# MRCS-CSNK.net
KiCad netlist of a schematic drawn in EAGLE
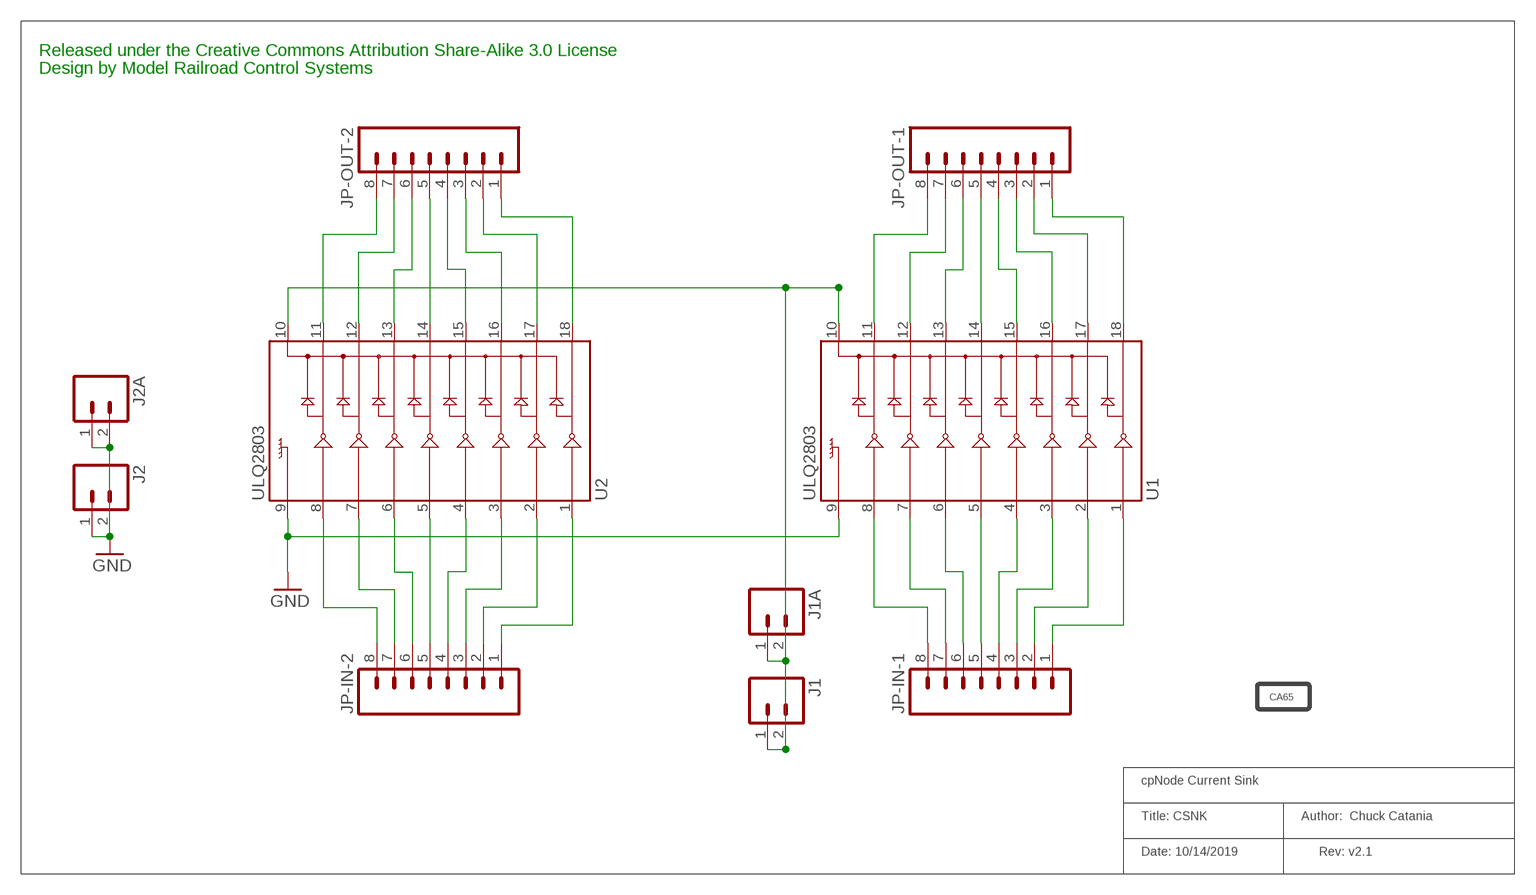
[diagram p0: schematic, sheet 1]

(export (version "E")
  (design (tool "Eeschema 10.0.6"))
  (components
    (comp (ref "J1")
      (value "CONNECTOR-M021X02-LOCK")
      (footprint "eagle-import:1X02_LOCK")
      (libsource (lib "eagle-import") (part "CONNECTOR-M021X02-LOCK"))
    )
    (comp (ref "J1A")
      (value "CONNECTOR-M023.5MM-LOCK")
      (footprint "eagle-import:SCREWTERMINAL-3.5MM-2_LOCK")
      (libsource (lib "eagle-import") (part "CONNECTOR-M023.5MM-LOCK"))
    )
    (comp (ref "J2")
      (value "CONNECTOR-M021X02-LOCK")
      (footprint "eagle-import:1X02_LOCK")
      (libsource (lib "eagle-import") (part "CONNECTOR-M021X02-LOCK"))
    )
    (comp (ref "J2A")
      (value "CONNECTOR-M023.5MM-LOCK")
      (footprint "eagle-import:SCREWTERMINAL-3.5MM-2_LOCK")
      (libsource (lib "eagle-import") (part "CONNECTOR-M023.5MM-LOCK"))
    )
    (comp (ref "JP-IN-1")
      (value "CONNECTOR-M08LOCK")
      (footprint "eagle-import:1X08_LOCK")
      (libsource (lib "eagle-import") (part "CONNECTOR-M08LOCK"))
    )
    (comp (ref "JP-IN-2")
      (value "CONNECTOR-M08LOCK")
      (footprint "eagle-import:1X08_LOCK")
      (libsource (lib "eagle-import") (part "CONNECTOR-M08LOCK"))
    )
    (comp (ref "JP-OUT-1")
      (value "CONNECTOR-M08LOCK")
      (footprint "eagle-import:1X08_LOCK")
      (libsource (lib "eagle-import") (part "CONNECTOR-M08LOCK"))
    )
    (comp (ref "JP-OUT-2")
      (value "CONNECTOR-M08LOCK")
      (footprint "eagle-import:1X08_LOCK")
      (libsource (lib "eagle-import") (part "CONNECTOR-M08LOCK"))
    )
    (comp (ref "PROP65")
      (value "DOC-CA65B")
      (footprint "eagle-import:CA-PROP65-BACK")
      (libsource (lib "eagle-import") (part "DOC-CA65B"))
    )
    (comp (ref "U1")
      (value "ULQ2803")
      (footprint "eagle-import:DIL18")
      (libsource (lib "eagle-import") (part "ULN2803DIP"))
    )
    (comp (ref "U2")
      (value "ULQ2803")
      (footprint "eagle-import:DIL18")
      (libsource (lib "eagle-import") (part "ULN2803DIP"))
    )
  )
  (nets
    (net (code "1") (name "GND") (class "Default")
      (node (ref "J2") (pin "1") (pinfunction "A_1") (pintype "passive"))
      (node (ref "J2") (pin "2") (pinfunction "B_2") (pintype "passive"))
      (node (ref "J2A") (pin "1") (pinfunction "A_1") (pintype "passive"))
      (node (ref "J2A") (pin "2") (pinfunction "B_2") (pintype "passive"))
      (node (ref "U1") (pin "9") (pinfunction "9_9") (pintype "bidirectional"))
      (node (ref "U2") (pin "9") (pinfunction "9_9") (pintype "bidirectional"))
    )
    (net (code "2") (name "Net-(J1-A)") (class "Default")
      (node (ref "J1") (pin "1") (pinfunction "A_1") (pintype "passive"))
      (node (ref "J1") (pin "2") (pinfunction "B_2") (pintype "passive"))
      (node (ref "J1A") (pin "1") (pinfunction "A_1") (pintype "passive"))
      (node (ref "J1A") (pin "2") (pinfunction "B_2") (pintype "passive"))
      (node (ref "U1") (pin "10") (pinfunction "10_10") (pintype "bidirectional"))
      (node (ref "U2") (pin "10") (pinfunction "10_10") (pintype "bidirectional"))
    )
    (net (code "3") (name "Net-(JP-IN-1-Pad1)") (class "Default")
      (node (ref "JP-IN-1") (pin "1") (pinfunction "1_1") (pintype "passive"))
      (node (ref "U1") (pin "1") (pinfunction "1_1") (pintype "bidirectional"))
    )
    (net (code "4") (name "Net-(JP-IN-1-Pad2)") (class "Default")
      (node (ref "JP-IN-1") (pin "2") (pinfunction "2_2") (pintype "passive"))
      (node (ref "U1") (pin "2") (pinfunction "2_2") (pintype "bidirectional"))
    )
    (net (code "5") (name "Net-(JP-IN-1-Pad3)") (class "Default")
      (node (ref "JP-IN-1") (pin "3") (pinfunction "3_3") (pintype "passive"))
      (node (ref "U1") (pin "3") (pinfunction "3_3") (pintype "bidirectional"))
    )
    (net (code "6") (name "Net-(JP-IN-1-Pad4)") (class "Default")
      (node (ref "JP-IN-1") (pin "4") (pinfunction "4_4") (pintype "passive"))
      (node (ref "U1") (pin "4") (pinfunction "4_4") (pintype "bidirectional"))
    )
    (net (code "7") (name "Net-(JP-IN-1-Pad5)") (class "Default")
      (node (ref "JP-IN-1") (pin "5") (pinfunction "5_5") (pintype "passive"))
      (node (ref "U1") (pin "5") (pinfunction "5_5") (pintype "bidirectional"))
    )
    (net (code "8") (name "Net-(JP-IN-1-Pad6)") (class "Default")
      (node (ref "JP-IN-1") (pin "6") (pinfunction "6_6") (pintype "passive"))
      (node (ref "U1") (pin "6") (pinfunction "6_6") (pintype "bidirectional"))
    )
    (net (code "9") (name "Net-(JP-IN-1-Pad7)") (class "Default")
      (node (ref "JP-IN-1") (pin "7") (pinfunction "7_7") (pintype "passive"))
      (node (ref "U1") (pin "7") (pinfunction "7_7") (pintype "bidirectional"))
    )
    (net (code "10") (name "Net-(JP-IN-1-Pad8)") (class "Default")
      (node (ref "JP-IN-1") (pin "8") (pinfunction "8_8") (pintype "passive"))
      (node (ref "U1") (pin "8") (pinfunction "8_8") (pintype "bidirectional"))
    )
    (net (code "11") (name "Net-(JP-IN-2-Pad1)") (class "Default")
      (node (ref "JP-IN-2") (pin "1") (pinfunction "1_1") (pintype "passive"))
      (node (ref "U2") (pin "1") (pinfunction "1_1") (pintype "bidirectional"))
    )
    (net (code "12") (name "Net-(JP-IN-2-Pad2)") (class "Default")
      (node (ref "JP-IN-2") (pin "2") (pinfunction "2_2") (pintype "passive"))
      (node (ref "U2") (pin "2") (pinfunction "2_2") (pintype "bidirectional"))
    )
    (net (code "13") (name "Net-(JP-IN-2-Pad3)") (class "Default")
      (node (ref "JP-IN-2") (pin "3") (pinfunction "3_3") (pintype "passive"))
      (node (ref "U2") (pin "3") (pinfunction "3_3") (pintype "bidirectional"))
    )
    (net (code "14") (name "Net-(JP-IN-2-Pad4)") (class "Default")
      (node (ref "JP-IN-2") (pin "4") (pinfunction "4_4") (pintype "passive"))
      (node (ref "U2") (pin "4") (pinfunction "4_4") (pintype "bidirectional"))
    )
    (net (code "15") (name "Net-(JP-IN-2-Pad5)") (class "Default")
      (node (ref "JP-IN-2") (pin "5") (pinfunction "5_5") (pintype "passive"))
      (node (ref "U2") (pin "5") (pinfunction "5_5") (pintype "bidirectional"))
    )
    (net (code "16") (name "Net-(JP-IN-2-Pad6)") (class "Default")
      (node (ref "JP-IN-2") (pin "6") (pinfunction "6_6") (pintype "passive"))
      (node (ref "U2") (pin "6") (pinfunction "6_6") (pintype "bidirectional"))
    )
    (net (code "17") (name "Net-(JP-IN-2-Pad7)") (class "Default")
      (node (ref "JP-IN-2") (pin "7") (pinfunction "7_7") (pintype "passive"))
      (node (ref "U2") (pin "7") (pinfunction "7_7") (pintype "bidirectional"))
    )
    (net (code "18") (name "Net-(JP-IN-2-Pad8)") (class "Default")
      (node (ref "JP-IN-2") (pin "8") (pinfunction "8_8") (pintype "passive"))
      (node (ref "U2") (pin "8") (pinfunction "8_8") (pintype "bidirectional"))
    )
    (net (code "19") (name "Net-(JP-OUT-1-Pad1)") (class "Default")
      (node (ref "JP-OUT-1") (pin "1") (pinfunction "1_1") (pintype "passive"))
      (node (ref "U1") (pin "18") (pinfunction "18_18") (pintype "bidirectional"))
    )
    (net (code "20") (name "Net-(JP-OUT-1-Pad2)") (class "Default")
      (node (ref "JP-OUT-1") (pin "2") (pinfunction "2_2") (pintype "passive"))
      (node (ref "U1") (pin "17") (pinfunction "17_17") (pintype "bidirectional"))
    )
    (net (code "21") (name "Net-(JP-OUT-1-Pad3)") (class "Default")
      (node (ref "JP-OUT-1") (pin "3") (pinfunction "3_3") (pintype "passive"))
      (node (ref "U1") (pin "16") (pinfunction "16_16") (pintype "bidirectional"))
    )
    (net (code "22") (name "Net-(JP-OUT-1-Pad4)") (class "Default")
      (node (ref "JP-OUT-1") (pin "4") (pinfunction "4_4") (pintype "passive"))
      (node (ref "U1") (pin "15") (pinfunction "15_15") (pintype "bidirectional"))
    )
    (net (code "23") (name "Net-(JP-OUT-1-Pad5)") (class "Default")
      (node (ref "JP-OUT-1") (pin "5") (pinfunction "5_5") (pintype "passive"))
      (node (ref "U1") (pin "14") (pinfunction "14_14") (pintype "bidirectional"))
    )
    (net (code "24") (name "Net-(JP-OUT-1-Pad6)") (class "Default")
      (node (ref "JP-OUT-1") (pin "6") (pinfunction "6_6") (pintype "passive"))
      (node (ref "U1") (pin "13") (pinfunction "13_13") (pintype "bidirectional"))
    )
    (net (code "25") (name "Net-(JP-OUT-1-Pad7)") (class "Default")
      (node (ref "JP-OUT-1") (pin "7") (pinfunction "7_7") (pintype "passive"))
      (node (ref "U1") (pin "12") (pinfunction "12_12") (pintype "bidirectional"))
    )
    (net (code "26") (name "Net-(JP-OUT-1-Pad8)") (class "Default")
      (node (ref "JP-OUT-1") (pin "8") (pinfunction "8_8") (pintype "passive"))
      (node (ref "U1") (pin "11") (pinfunction "11_11") (pintype "bidirectional"))
    )
    (net (code "27") (name "Net-(JP-OUT-2-Pad1)") (class "Default")
      (node (ref "JP-OUT-2") (pin "1") (pinfunction "1_1") (pintype "passive"))
      (node (ref "U2") (pin "18") (pinfunction "18_18") (pintype "bidirectional"))
    )
    (net (code "28") (name "Net-(JP-OUT-2-Pad2)") (class "Default")
      (node (ref "JP-OUT-2") (pin "2") (pinfunction "2_2") (pintype "passive"))
      (node (ref "U2") (pin "17") (pinfunction "17_17") (pintype "bidirectional"))
    )
    (net (code "29") (name "Net-(JP-OUT-2-Pad3)") (class "Default")
      (node (ref "JP-OUT-2") (pin "3") (pinfunction "3_3") (pintype "passive"))
      (node (ref "U2") (pin "16") (pinfunction "16_16") (pintype "bidirectional"))
    )
    (net (code "30") (name "Net-(JP-OUT-2-Pad4)") (class "Default")
      (node (ref "JP-OUT-2") (pin "4") (pinfunction "4_4") (pintype "passive"))
      (node (ref "U2") (pin "15") (pinfunction "15_15") (pintype "bidirectional"))
    )
    (net (code "31") (name "Net-(JP-OUT-2-Pad5)") (class "Default")
      (node (ref "JP-OUT-2") (pin "5") (pinfunction "5_5") (pintype "passive"))
      (node (ref "U2") (pin "14") (pinfunction "14_14") (pintype "bidirectional"))
    )
    (net (code "32") (name "Net-(JP-OUT-2-Pad6)") (class "Default")
      (node (ref "JP-OUT-2") (pin "6") (pinfunction "6_6") (pintype "passive"))
      (node (ref "U2") (pin "13") (pinfunction "13_13") (pintype "bidirectional"))
    )
    (net (code "33") (name "Net-(JP-OUT-2-Pad7)") (class "Default")
      (node (ref "JP-OUT-2") (pin "7") (pinfunction "7_7") (pintype "passive"))
      (node (ref "U2") (pin "12") (pinfunction "12_12") (pintype "bidirectional"))
    )
    (net (code "34") (name "Net-(JP-OUT-2-Pad8)") (class "Default")
      (node (ref "JP-OUT-2") (pin "8") (pinfunction "8_8") (pintype "passive"))
      (node (ref "U2") (pin "11") (pinfunction "11_11") (pintype "bidirectional"))
    )
  )
)
